# ife19_TS_TSAL-Discharge-TSMP.net
KiCad netlist of a schematic drawn in Altium Designer
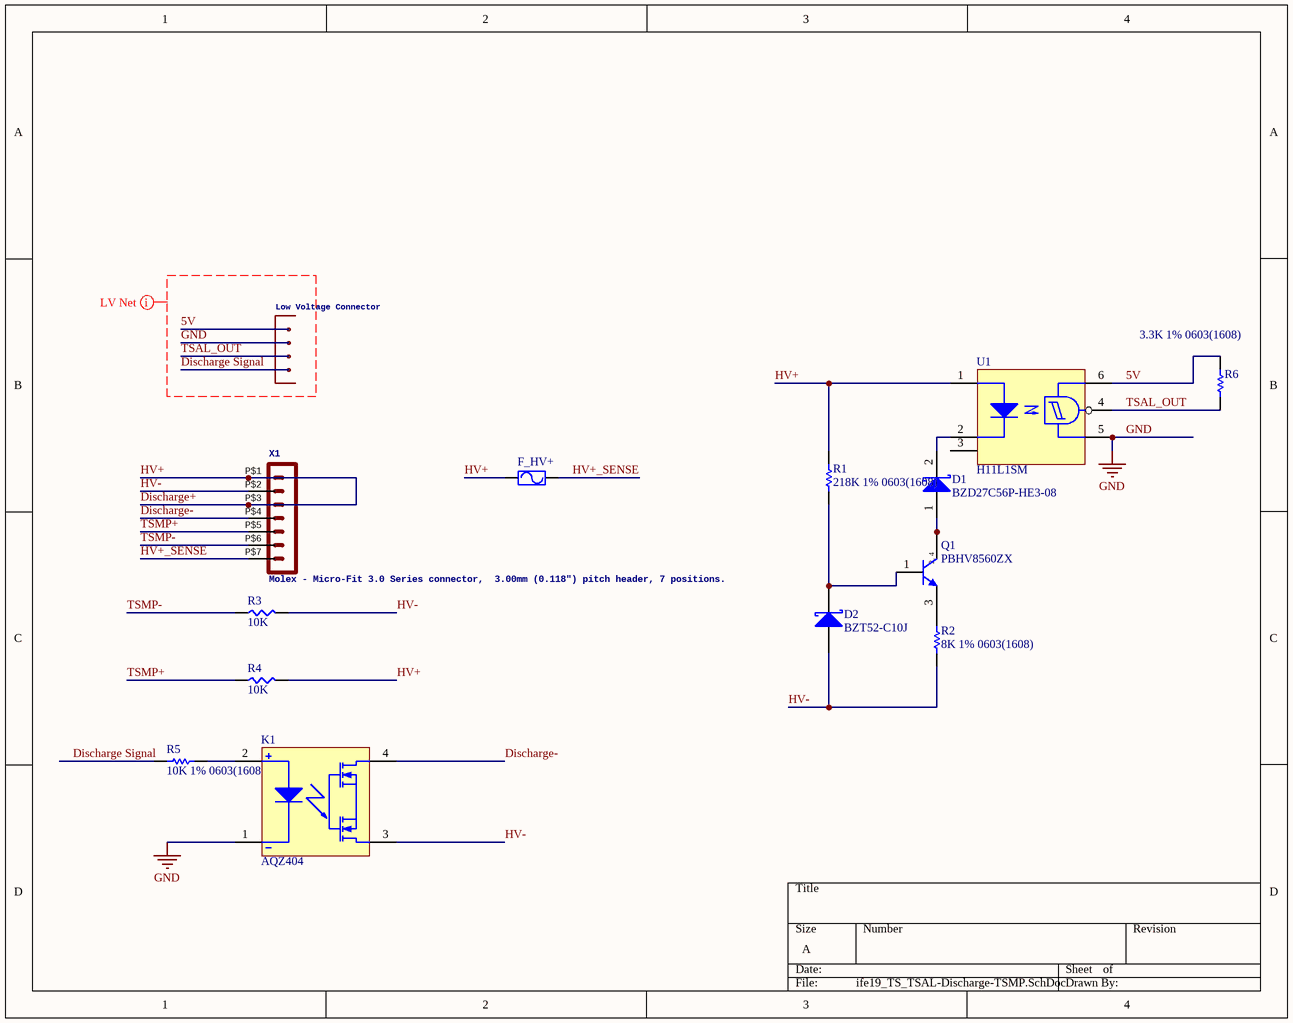
[diagram p0: ife19_TS_TSAL-Discharge-TSMP.SchDoc]

(export (version "E")
  (design (tool "Eeschema 10.0.6"))
  (components
    (comp (ref "D1")
      (value "BZD27C56P-HE3-08")
      (footprint "VISH-DO-219AB_V")
      (fields (field (name "PARTNUMBER") "SL03-GS08CT") (field (name "MANUFACTURER") "Vishay Semiconductor"))
      (libsource (lib "Altium Content Vault") (part "DSKY-AK-2"))
    )
    (comp (ref "D2")
      (value "BZT52-C10J")
      (footprint "FAIR-SOD123-2_V")
      (description "Diode Schottky 30V 0.5A 2-Pin SOD-123 T/R")
      (fields (field (name "MANUFACTURER") "Fairchild"))
      (libsource (lib "") (part "DSKY-AK-2_1"))
    )
    (comp (ref "F_HV+")
      (value "FUSE_885")
      (footprint "FUSE_885")
      (libsource (lib "altium-import") (part "root_0_FUSE_885_"))
    )
    (comp (ref "K1")
      (value "AQZ404")
      (footprint "PNSC-SIL4_V")
      (fields (field (name "MANUFACTURER") "Panasonic"))
      (libsource (lib "Altium Content Vault") (part "PNSC-AQZX0X-SIL4"))
    )
    (comp (ref "Low Voltage Connector")
      (value "~")
      (footprint "505575-04")
      (fields (field (name "LIBRARYNAME") "MOLEX Micro-Lock"))
      (libsource (lib "MOLEX Micro-Lock (2)") (part "505575-04"))
    )
    (comp (ref "Q1")
      (value "PBHV8560ZX")
      (footprint "NXP-SOT223_L")
      (description "NPN Medium Power Transistor, 60 V, 1 A, -55 to 150 degC, 4-Pin SOT223, RoHS, Tape and Reel")
      (fields (field (name "MANUFACTURER") "NXP Semiconductors"))
      (libsource (lib "Altium Content Vault") (part "BJT-NPN-BCEC-4"))
    )
    (comp (ref "R1")
      (value "218K 1% 0603(1608)")
      (footprint "RESC0603(1608)_L")
      (description "249K 0.1W 1% 0603 (1608 Metric)  SMD")
      (fields (field (name "POWER") "0.1 W") (field (name "TOLERANCE") "1 %"))
      (libsource (lib "Altium Content Vault") (part "RES"))
    )
    (comp (ref "R2")
      (value "8K 1% 0603(1608)")
      (footprint "RESC0603(1608)_L")
      (description "348K 0.1W 1% 0603 (1608 Metric)  SMD")
      (fields (field (name "TOLERANCE") "1 %") (field (name "POWER") "0.1 W"))
      (libsource (lib "Altium Content Vault") (part "RES"))
    )
    (comp (ref "R3")
      (value "10K")
      (footprint "Ohmite 45")
      (libsource (lib "IFE_Resistors (2)") (part "Ohmite 40 Series"))
    )
    (comp (ref "R4")
      (value "10K")
      (footprint "Ohmite 45")
      (libsource (lib "IFE_Resistors (2)") (part "Ohmite 40 Series"))
    )
    (comp (ref "R5")
      (value "10K 1% 0603(1608)")
      (footprint "RESC0603(1608)_L")
      (description "249K 0.1W 1% 0603 (1608 Metric)  SMD")
      (fields (field (name "POWER") "0.1 W") (field (name "TOLERANCE") "1 %"))
      (libsource (lib "Altium Content Vault") (part "RES"))
    )
    (comp (ref "R6")
      (value "3.3K 1% 0603(1608)")
      (footprint "RESC0603(1608)_L")
      (description "249K 0.1W 1% 0603 (1608 Metric)  SMD")
      (fields (field (name "POWER") "0.1 W") (field (name "TOLERANCE") "1 %"))
      (libsource (lib "Altium Content Vault") (part "RES"))
    )
    (comp (ref "U1")
      (value "H11L1SM")
      (footprint "FAIR-SMT-6_V")
      (description "Schmitt Trigger Output Optocoupler, 3 to 15 V, -40 to 85 degC, 6-Pin SMT, RoHS, Tube")
      (fields (field (name "MANUFACTURER") "Fairchild Semiconductor"))
      (libsource (lib "Altium Content Vault") (part "FAIR-H11L1M-6"))
    )
    (comp (ref "X1")
      (value "Molex - Micro-Fit 3.0 Series connector,  3.00mm (0.118\") pitch header, 7 positions.")
      (footprint "43650-0724")
      (libsource (lib "altium-import") (part "root_0_POS7_MF43650-0724_"))
    )
  )
  (nets
    (net (code "1") (name "/5V") (class "Default")
      (node (ref "Low Voltage Connector") (pin "1") (pinfunction "1_1") (pintype "passive"))
      (node (ref "R6") (pin "2") (pinfunction "2_2") (pintype "passive"))
      (node (ref "U1") (pin "6") (pinfunction "VCC_6") (pintype "power_in"))
    )
    (net (code "2") (name "/Discharge Signal") (class "Default")
      (node (ref "Low Voltage Connector") (pin "4") (pinfunction "4_4") (pintype "passive"))
      (node (ref "R5") (pin "2") (pinfunction "2_2") (pintype "passive"))
    )
    (net (code "3") (name "/Discharge+") (class "Default")
      (node (ref "F_HV+") (pin "2") (pinfunction "2_2") (pintype "passive"))
      (node (ref "R1") (pin "2") (pinfunction "2_2") (pintype "passive"))
      (node (ref "R4") (pin "2") (pinfunction "2_2") (pintype "passive"))
      (node (ref "U1") (pin "1") (pinfunction "ANODE_1") (pintype "passive"))
      (node (ref "X1") (pin "P$1") (pinfunction "1_P$1") (pintype "passive"))
      (node (ref "X1") (pin "P$3") (pinfunction "3_P$3") (pintype "passive"))
    )
    (net (code "4") (name "/Discharge-") (class "Default")
      (node (ref "K1") (pin "4") (pinfunction "4_4") (pintype "passive"))
      (node (ref "X1") (pin "P$4") (pinfunction "4_P$4") (pintype "passive"))
    )
    (net (code "5") (name "/HV+_SENSE") (class "Default")
      (node (ref "F_HV+") (pin "1") (pinfunction "1_1") (pintype "passive"))
      (node (ref "X1") (pin "P$7") (pinfunction "7_P$7") (pintype "passive"))
    )
    (net (code "6") (name "/HV-") (class "Default")
      (node (ref "D2") (pin "1") (pinfunction "A_1") (pintype "passive"))
      (node (ref "K1") (pin "3") (pinfunction "3_3") (pintype "passive"))
      (node (ref "R2") (pin "1") (pinfunction "1_1") (pintype "passive"))
      (node (ref "R3") (pin "2") (pinfunction "2_2") (pintype "passive"))
      (node (ref "X1") (pin "P$2") (pinfunction "2_P$2") (pintype "passive"))
    )
    (net (code "7") (name "/TSAL_OUT") (class "Default")
      (node (ref "Low Voltage Connector") (pin "3") (pinfunction "3_3") (pintype "passive"))
      (node (ref "R6") (pin "1") (pinfunction "1_1") (pintype "passive"))
      (node (ref "U1") (pin "4") (pinfunction "VO_4") (pintype "open_collector"))
    )
    (net (code "8") (name "/TSMP+") (class "Default")
      (node (ref "R4") (pin "1") (pinfunction "1_1") (pintype "passive"))
      (node (ref "X1") (pin "P$5") (pinfunction "5_P$5") (pintype "passive"))
    )
    (net (code "9") (name "/TSMP-") (class "Default")
      (node (ref "R3") (pin "1") (pinfunction "1_1") (pintype "passive"))
      (node (ref "X1") (pin "P$6") (pinfunction "6_P$6") (pintype "passive"))
    )
    (net (code "10") (name "GND") (class "Default")
      (node (ref "K1") (pin "1") (pinfunction "-_1") (pintype "passive"))
      (node (ref "Low Voltage Connector") (pin "2") (pinfunction "2_2") (pintype "passive"))
      (node (ref "U1") (pin "5") (pinfunction "GND_5") (pintype "power_in"))
    )
    (net (code "11") (name "Net-(D1-A)") (class "Default")
      (node (ref "D1") (pin "1") (pinfunction "A_1") (pintype "passive"))
      (node (ref "Q1") (pin "2") (pinfunction "C_2") (pintype "passive"))
      (node (ref "Q1") (pin "4") (pinfunction "C_4") (pintype "passive"))
    )
    (net (code "12") (name "Net-(D1-K)") (class "Default")
      (node (ref "D1") (pin "2") (pinfunction "K_2") (pintype "passive"))
      (node (ref "U1") (pin "2") (pinfunction "CATHODE_2") (pintype "passive"))
    )
    (net (code "13") (name "Net-(D2-K)") (class "Default")
      (node (ref "D2") (pin "2") (pinfunction "K_2") (pintype "passive"))
      (node (ref "Q1") (pin "1") (pinfunction "B_1") (pintype "passive"))
      (node (ref "R1") (pin "1") (pinfunction "1_1") (pintype "passive"))
    )
    (net (code "14") (name "Net-(K1-+)") (class "Default")
      (node (ref "K1") (pin "2") (pinfunction "+_2") (pintype "passive"))
      (node (ref "R5") (pin "1") (pinfunction "1_1") (pintype "passive"))
    )
    (net (code "15") (name "Net-(Q1-E)") (class "Default")
      (node (ref "Q1") (pin "3") (pinfunction "E_3") (pintype "passive"))
      (node (ref "R2") (pin "2") (pinfunction "2_2") (pintype "passive"))
    )
    (net (code "16") (name "unconnected-(U1-NC-Pad3)") (class "Default")
      (node (ref "U1") (pin "3") (pinfunction "NC_3") (pintype "passive"))
    )
  )
)
